# POWER.net
KiCad netlist of a schematic drawn in Altium Designer
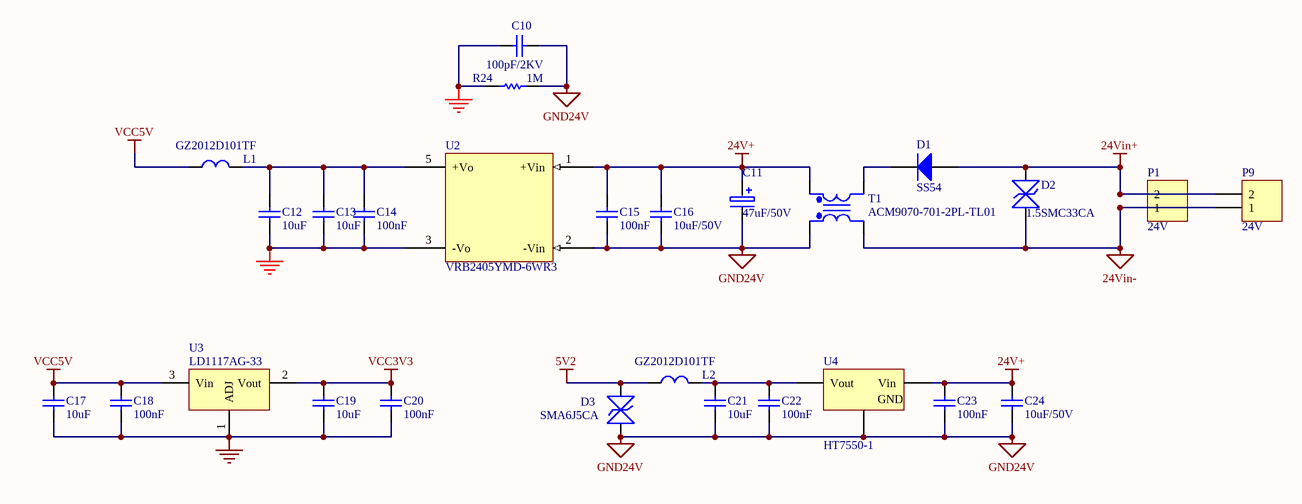
[diagram p0: POWER.SchDoc]

(export (version "E")
  (design (tool "Eeschema 10.0.6"))
  (components
    (comp (ref "C10")
      (value "100pF/2KV")
      (footprint "1206_C")
      (description "Capacitor")
      (fields (field (name "PUBLISHER") "Altium Limited"))
      (libsource (lib "Miscellaneous Devices") (part "Cap"))
    )
    (comp (ref "C11")
      (value "47uF/50V")
      (footprint "CD1/2")
      (description "Electrolytic Capacitor")
      (libsource (lib "*") (part "CD1"))
    )
    (comp (ref "C12")
      (value "10uF")
      (footprint "0805_C")
      (description "贴片电容")
      (libsource (lib "Miscellaneous Devices LC") (part "0805 10uF (106) 10% 25V"))
    )
    (comp (ref "C13")
      (value "10uF")
      (footprint "0805_C")
      (description "贴片电容")
      (libsource (lib "Miscellaneous Devices LC") (part "0805 10uF (106) 10% 25V"))
    )
    (comp (ref "C14")
      (value "100nF")
      (footprint "0805_C")
      (description "贴片电容")
      (libsource (lib "Miscellaneous Devices LC") (part "0805 100nF(104) 10% 50V"))
    )
    (comp (ref "C15")
      (value "100nF")
      (footprint "0805_C")
      (description "贴片电容")
      (libsource (lib "Miscellaneous Devices LC") (part "0805 100nF(104) 10% 50V"))
    )
    (comp (ref "C16")
      (value "10uF/50V")
      (footprint "1206_C")
      (description "贴片电容")
      (libsource (lib "Miscellaneous Devices LC") (part "1206 10uF (106) 10% 50V"))
    )
    (comp (ref "C17")
      (value "10uF")
      (footprint "0805_C")
      (description "贴片电容")
      (libsource (lib "Miscellaneous Devices LC") (part "0805 10uF (106) 10% 25V"))
    )
    (comp (ref "C18")
      (value "100nF")
      (footprint "0805_C")
      (description "贴片电容")
      (libsource (lib "Miscellaneous Devices LC") (part "0805 100nF(104) 10% 50V"))
    )
    (comp (ref "C19")
      (value "10uF")
      (footprint "0805_C")
      (description "贴片电容")
      (libsource (lib "Miscellaneous Devices LC") (part "0805 10uF (106) 10% 25V"))
    )
    (comp (ref "C20")
      (value "100nF")
      (footprint "0805_C")
      (description "贴片电容")
      (libsource (lib "Miscellaneous Devices LC") (part "0805 100nF(104) 10% 50V"))
    )
    (comp (ref "C21")
      (value "10uF")
      (footprint "0805_C")
      (description "贴片电容")
      (libsource (lib "Miscellaneous Devices LC") (part "0805 10uF (106) 10% 25V"))
    )
    (comp (ref "C22")
      (value "100nF")
      (footprint "0805_C")
      (description "贴片电容")
      (libsource (lib "Miscellaneous Devices LC") (part "0805 100nF(104) 10% 50V"))
    )
    (comp (ref "C23")
      (value "100nF")
      (footprint "0805_C")
      (description "贴片电容")
      (libsource (lib "Miscellaneous Devices LC") (part "0805 100nF(104) 10% 50V"))
    )
    (comp (ref "C24")
      (value "10uF/50V")
      (footprint "1206_C")
      (description "贴片电容")
      (libsource (lib "Miscellaneous Devices LC") (part "1206 10uF (106) 10% 50V"))
    )
    (comp (ref "D1")
      (value "SS54")
      (footprint "SMA(DO-214AC)_S1")
      (description "二极管")
      (libsource (lib "Miscellaneous Devices LC") (part "SMA(DO-214AC) SS54"))
    )
    (comp (ref "D2")
      (value "1.5SMC33CA")
      (footprint "Miscellaneous Devices LC:SMC(DO-214AB)_S1")
      (libsource (lib "IC") (part "TVS"))
    )
    (comp (ref "D3") (value "SMA6J5CA") (footprint "SMA") (libsource (lib "IC") (part "TVS")))
    (comp (ref "L1") (value "GZ2012D101TF") (footprint "0805_L") (libsource (lib "Devices") (part "L1")))
    (comp (ref "L2") (value "GZ2012D101TF") (footprint "0805_L") (libsource (lib "Devices") (part "L1")))
    (comp (ref "P1")
      (value "24V")
      (footprint "mc1.5/2-st-3.81")
      (description "Header, 2-Pin")
      (fields (field (name "PUBLISHER") "Altium Limited"))
      (libsource (lib "Miscellaneous Connectors") (part "Header 2"))
    )
    (comp (ref "P9")
      (value "24V")
      (footprint "mc1.5/2-st-3.81")
      (description "Header, 2-Pin")
      (fields (field (name "PUBLISHER") "Altium Limited"))
      (libsource (lib "Miscellaneous Connectors") (part "Header 2"))
    )
    (comp (ref "R24")
      (value "1M")
      (footprint "1206_R")
      (description "Resistor")
      (fields (field (name "PUBLISHER") "Altium Limited"))
      (libsource (lib "Miscellaneous Devices") (part "Res1"))
    )
    (comp (ref "T1")
      (value "ACM9070-701-2PL-TL01")
      (footprint "ACM1211")
      (description "TDP ACP3225 Common Mode Filters")
      (fields (field (name "PUBLISHER") "Altium Limited"))
      (libsource (lib "Sheet1") (part "ACP3225"))
    )
    (comp (ref "U2") (value "VRB2405YMD-6WR3") (footprint "DC/DC-1X1") (libsource (lib "*") (part "48S5")))
    (comp (ref "U3")
      (value "LD1117AG-33")
      (footprint "SOT-223")
      (description "3-Terminal Adjustable Positive Voltage Regulator")
      (libsource (lib "稳压器件") (part "LM1117"))
    )
    (comp (ref "U4")
      (value "HT7550-1")
      (footprint "SOT-89(SOT-89-3)")
      (description "低压差线性稳压(LDO)")
      (libsource (lib "Miscellaneous Devices LC") (part "SOT-89 HT7550-1"))
    )
  )
  (nets
    (net (code "1") (name "5V2") (class "Default")
      (node (ref "D3") (pin "1") (pinfunction "1_1") (pintype "passive"))
      (node (ref "L2") (pin "2") (pinfunction "2_2") (pintype "passive"))
    )
    (net (code "2") (name "24V+") (class "Default")
      (node (ref "C11") (pin "1") (pinfunction "1_1") (pintype "passive"))
      (node (ref "C15") (pin "2") (pinfunction "2_2") (pintype "passive"))
      (node (ref "C16") (pin "2") (pinfunction "2_2") (pintype "passive"))
      (node (ref "C23") (pin "2") (pinfunction "2_2") (pintype "passive"))
      (node (ref "C24") (pin "2") (pinfunction "2_2") (pintype "passive"))
      (node (ref "T1") (pin "2") (pinfunction "Pri+_2") (pintype "passive"))
      (node (ref "U2") (pin "1") (pinfunction "+Vin_1") (pintype "input"))
      (node (ref "U4") (pin "2") (pinfunction "Vin_2") (pintype "passive"))
    )
    (net (code "3") (name "24Vin+") (class "Default")
      (node (ref "D1") (pin "1") (pinfunction "A_1") (pintype "passive"))
      (node (ref "D2") (pin "2") (pinfunction "2_2") (pintype "passive"))
      (node (ref "P1") (pin "2") (pinfunction "2_2") (pintype "passive"))
      (node (ref "P9") (pin "2") (pinfunction "2_2") (pintype "passive"))
    )
    (net (code "4") (name "24Vin-") (class "Default")
      (node (ref "D2") (pin "1") (pinfunction "1_1") (pintype "passive"))
      (node (ref "P1") (pin "1") (pinfunction "1_1") (pintype "passive"))
      (node (ref "P9") (pin "1") (pinfunction "1_1") (pintype "passive"))
      (node (ref "T1") (pin "4") (pinfunction "Sec-_4") (pintype "passive"))
    )
    (net (code "5") (name "GND") (class "Default")
      (node (ref "C10") (pin "1") (pinfunction "1_1") (pintype "passive"))
      (node (ref "C12") (pin "1") (pinfunction "1_1") (pintype "passive"))
      (node (ref "C13") (pin "1") (pinfunction "1_1") (pintype "passive"))
      (node (ref "C14") (pin "1") (pinfunction "1_1") (pintype "passive"))
      (node (ref "C17") (pin "1") (pinfunction "1_1") (pintype "passive"))
      (node (ref "C18") (pin "1") (pinfunction "1_1") (pintype "passive"))
      (node (ref "C19") (pin "1") (pinfunction "1_1") (pintype "passive"))
      (node (ref "C20") (pin "1") (pinfunction "1_1") (pintype "passive"))
      (node (ref "R24") (pin "1") (pinfunction "1_1") (pintype "passive"))
      (node (ref "U2") (pin "3") (pinfunction "-Vo_3") (pintype "power_in"))
      (node (ref "U3") (pin "1") (pinfunction "ADJ_1") (pintype "passive"))
    )
    (net (code "6") (name "GND24V") (class "Default")
      (node (ref "C10") (pin "2") (pinfunction "2_2") (pintype "passive"))
      (node (ref "C11") (pin "2") (pinfunction "2_2") (pintype "passive"))
      (node (ref "C15") (pin "1") (pinfunction "1_1") (pintype "passive"))
      (node (ref "C16") (pin "1") (pinfunction "1_1") (pintype "passive"))
      (node (ref "C21") (pin "1") (pinfunction "1_1") (pintype "passive"))
      (node (ref "C22") (pin "1") (pinfunction "1_1") (pintype "passive"))
      (node (ref "C23") (pin "1") (pinfunction "1_1") (pintype "passive"))
      (node (ref "C24") (pin "1") (pinfunction "1_1") (pintype "passive"))
      (node (ref "D3") (pin "2") (pinfunction "2_2") (pintype "passive"))
      (node (ref "R24") (pin "2") (pinfunction "2_2") (pintype "passive"))
      (node (ref "T1") (pin "1") (pinfunction "Sec+_1") (pintype "passive"))
      (node (ref "U2") (pin "2") (pinfunction "-Vin_2") (pintype "input"))
      (node (ref "U4") (pin "1") (pinfunction "GND_1") (pintype "passive"))
    )
    (net (code "7") (name "NC") (class "Default")
      (node (ref "U2") (pin "4") (pinfunction "NC_4") (pintype "tri_state"))
    )
    (net (code "8") (name "Net-(D1-K)") (class "Default")
      (node (ref "D1") (pin "2") (pinfunction "K_2") (pintype "passive"))
      (node (ref "T1") (pin "3") (pinfunction "Pri-_3") (pintype "passive"))
    )
    (net (code "9") (name "Net-(U2-+Vo)") (class "Default")
      (node (ref "C12") (pin "2") (pinfunction "2_2") (pintype "passive"))
      (node (ref "C13") (pin "2") (pinfunction "2_2") (pintype "passive"))
      (node (ref "C14") (pin "2") (pinfunction "2_2") (pintype "passive"))
      (node (ref "L1") (pin "1") (pinfunction "1_1") (pintype "passive"))
      (node (ref "U2") (pin "5") (pinfunction "+Vo_5") (pintype "power_in"))
    )
    (net (code "10") (name "Net-(U4-Vout)") (class "Default")
      (node (ref "C21") (pin "2") (pinfunction "2_2") (pintype "passive"))
      (node (ref "C22") (pin "2") (pinfunction "2_2") (pintype "passive"))
      (node (ref "L2") (pin "1") (pinfunction "1_1") (pintype "passive"))
      (node (ref "U4") (pin "3") (pinfunction "Vout_3") (pintype "passive"))
    )
    (net (code "11") (name "VCC3V3") (class "Default")
      (node (ref "C19") (pin "2") (pinfunction "2_2") (pintype "passive"))
      (node (ref "C20") (pin "2") (pinfunction "2_2") (pintype "passive"))
      (node (ref "U3") (pin "2") (pinfunction "Vout_2") (pintype "passive"))
    )
    (net (code "12") (name "VCC5V") (class "Default")
      (node (ref "C17") (pin "2") (pinfunction "2_2") (pintype "passive"))
      (node (ref "C18") (pin "2") (pinfunction "2_2") (pintype "passive"))
      (node (ref "L1") (pin "2") (pinfunction "2_2") (pintype "passive"))
      (node (ref "U3") (pin "3") (pinfunction "Vin_3") (pintype "passive"))
    )
  )
)
